# dual_output_buck_regulator.net
KiCad netlist of a schematic drawn in EAGLE
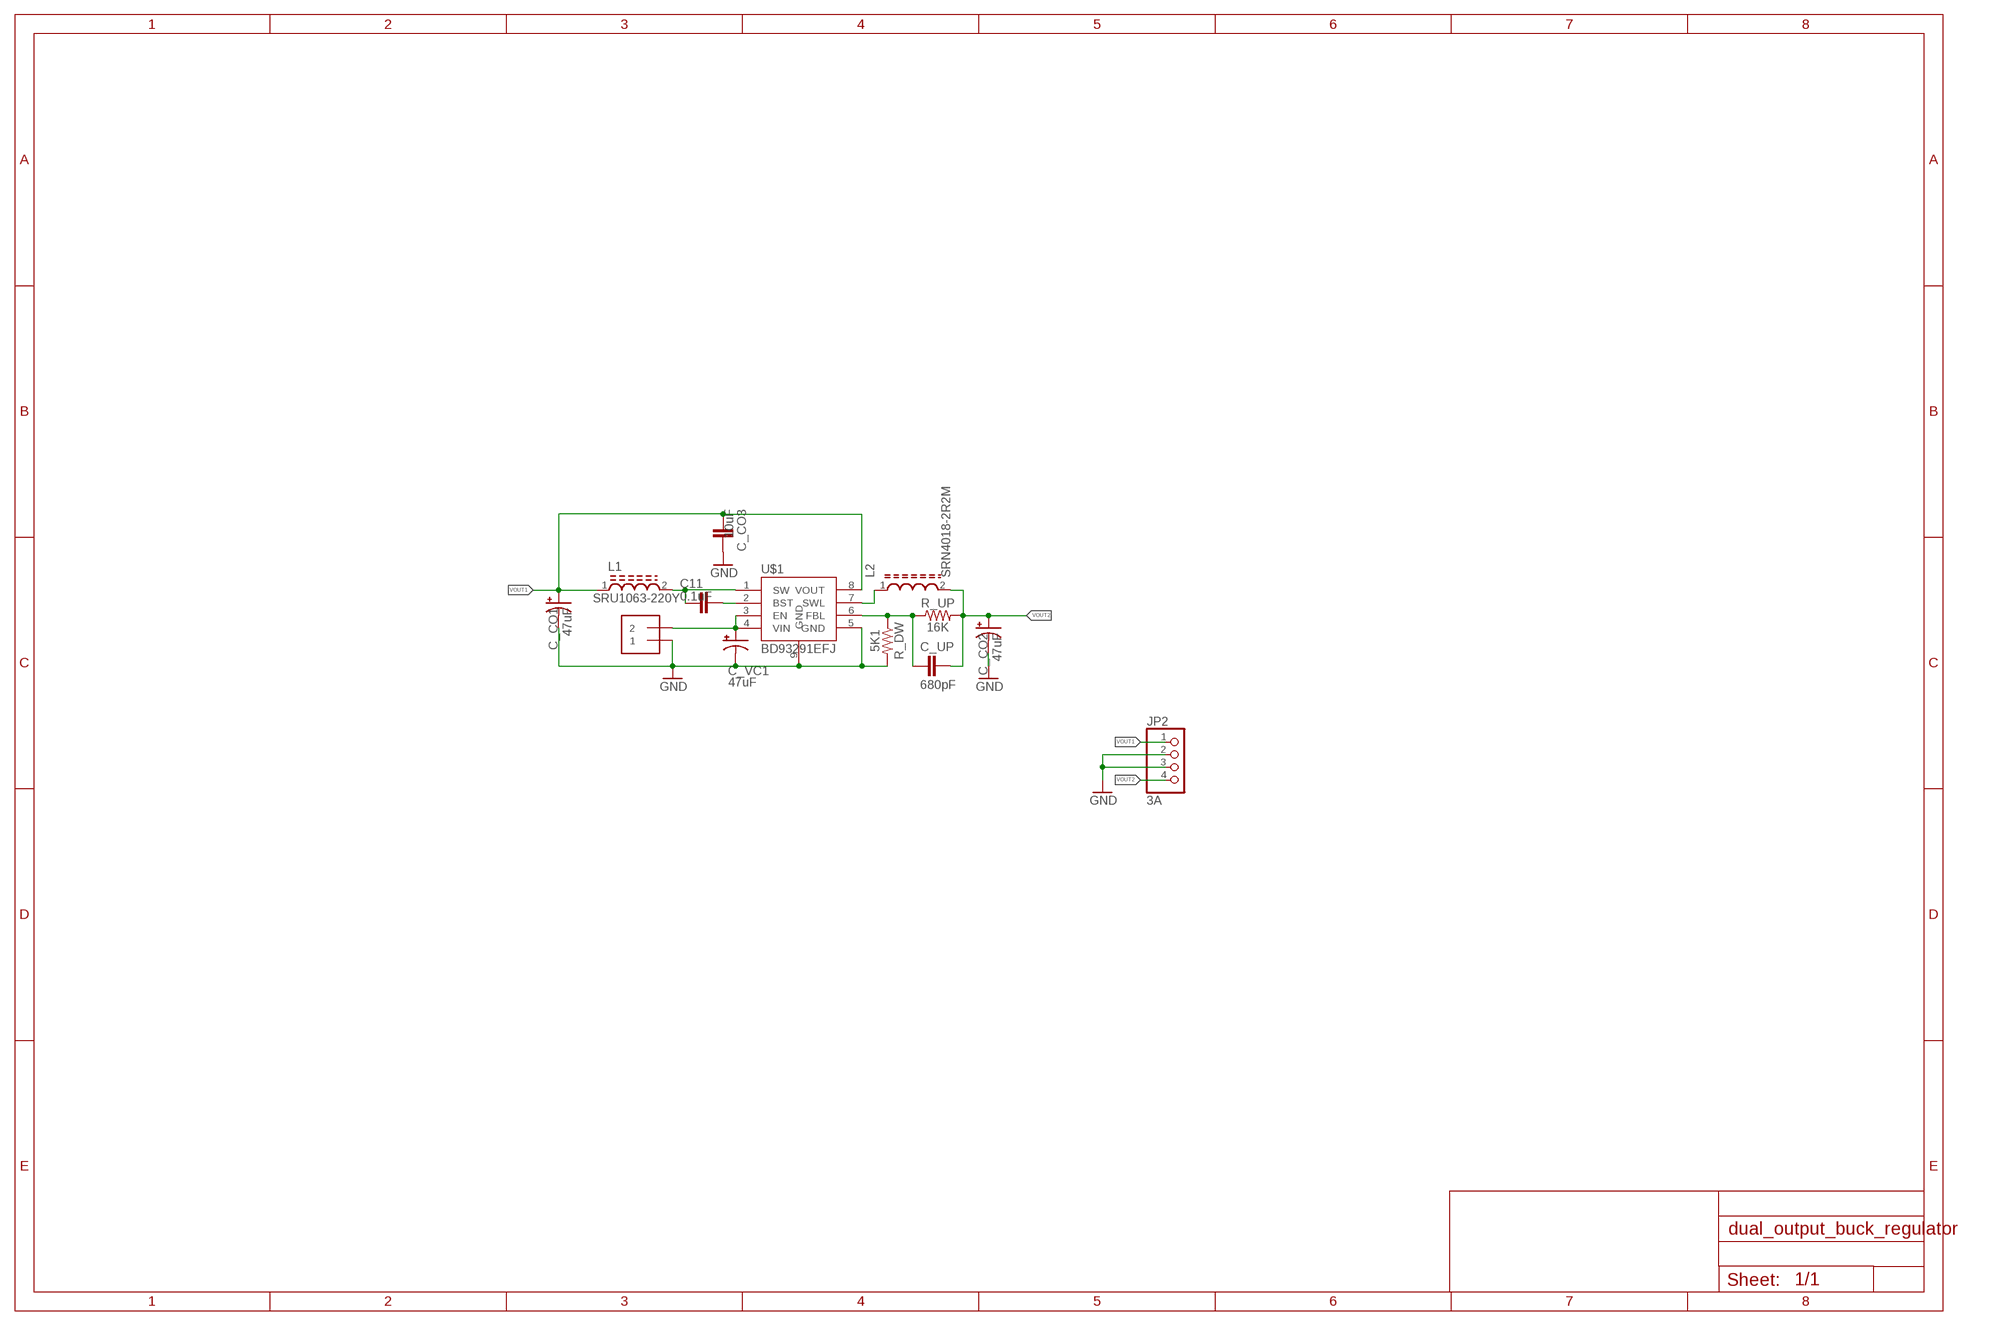
[diagram p0: schematic, sheet 1]

(export (version "E")
  (design (tool "Eeschema 10.0.6"))
  (components
    (comp (ref "C11")
      (value "0.1uF")
      (footprint "eagle-import:0603")
      (libsource (lib "eagle-import") (part "0.1UF-0603-25V-(+80/-20%)"))
    )
    (comp (ref "C_CO1")
      (value "47uF")
      (footprint "eagle-import:PANASONIC_C")
      (libsource (lib "eagle-import") (part "22UF-POLAR-PANASONIC_C-35V-20%"))
    )
    (comp (ref "C_CO2")
      (value "47uF")
      (footprint "eagle-import:PANASONIC_C")
      (libsource (lib "eagle-import") (part "22UF-POLAR-PANASONIC_C-35V-20%"))
    )
    (comp (ref "C_CO3")
      (value "10uF")
      (footprint "eagle-import:0603")
      (libsource (lib "eagle-import") (part "0.1UF-0603-25V-(+80/-20%)"))
    )
    (comp (ref "C_UP")
      (value "680pF")
      (footprint "eagle-import:0603")
      (libsource (lib "eagle-import") (part "0.1UF-0603-25V-(+80/-20%)"))
    )
    (comp (ref "C_VC1")
      (value "47uF")
      (footprint "eagle-import:PANASONIC_C")
      (libsource (lib "eagle-import") (part "22UF-POLAR-PANASONIC_C-35V-20%"))
    )
    (comp (ref "J1")
      (value "1X2-3.5MM")
      (footprint "eagle-import:1X2-3.5MM")
      (libsource (lib "eagle-import") (part "1X2-3.5MM"))
    )
    (comp (ref "JP2")
      (value "3A")
      (footprint "eagle-import:1X04")
      (libsource (lib "eagle-import") (part "PINHD-1X4"))
    )
    (comp (ref "L1")
      (value "SRU1063-220Y")
      (footprint "eagle-import:IND_SRU1063-220Y")
      (fields (field (name "MF") "Bourns"))
      (libsource (lib "eagle-import") (part "SRU1063-220Y"))
    )
    (comp (ref "L2")
      (value "SRN4018-2R2M")
      (footprint "eagle-import:INDP4040X180N")
      (fields (field (name "MF") "Bourns") (field (name "MP") "SRN4018-2R7M"))
      (libsource (lib "eagle-import") (part "SRN4018-2R7M"))
    )
    (comp (ref "R_DW")
      (value "5K1")
      (footprint "eagle-import:0603")
      (libsource (lib "eagle-import") (part "10KOHM-0603-1/10W-1%"))
    )
    (comp (ref "R_UP")
      (value "16K")
      (footprint "eagle-import:0603")
      (libsource (lib "eagle-import") (part "10KOHM-0603-1/10W-1%"))
    )
    (comp (ref "U$1")
      (value "BD93291EFJ")
      (footprint "eagle-import:SOIC127P600X100-9N")
      (libsource (lib "eagle-import") (part "BD93291EFJ"))
    )
  )
  (nets
    (net (code "1") (name "GND") (class "Default")
      (node (ref "C_CO1") (pin "-") (pinfunction "-_-") (pintype "passive"))
      (node (ref "C_CO2") (pin "-") (pinfunction "-_-") (pintype "passive"))
      (node (ref "C_CO3") (pin "1") (pinfunction "1_1") (pintype "passive"))
      (node (ref "C_VC1") (pin "-") (pinfunction "-_-") (pintype "passive"))
      (node (ref "J1") (pin "1") (pinfunction "1_1") (pintype "passive"))
      (node (ref "JP2") (pin "2") (pinfunction "2_2") (pintype "passive"))
      (node (ref "JP2") (pin "3") (pinfunction "3_3") (pintype "passive"))
      (node (ref "R_DW") (pin "2") (pinfunction "2_2") (pintype "passive"))
      (node (ref "U$1") (pin "5") (pinfunction "GND_5") (pintype "bidirectional"))
      (node (ref "U$1") (pin "9") (pinfunction "GND_9") (pintype "bidirectional"))
    )
    (net (code "2") (name "Net-(U$1-BST)") (class "Default")
      (node (ref "C11") (pin "1") (pinfunction "1_1") (pintype "passive"))
      (node (ref "U$1") (pin "2") (pinfunction "BST_2") (pintype "bidirectional"))
    )
    (net (code "3") (name "Net-(U$1-EN)") (class "Default")
      (node (ref "C_VC1") (pin "+") (pinfunction "+_+") (pintype "passive"))
      (node (ref "J1") (pin "2") (pinfunction "2_2") (pintype "passive"))
      (node (ref "U$1") (pin "3") (pinfunction "EN_3") (pintype "bidirectional"))
      (node (ref "U$1") (pin "4") (pinfunction "VIN_4") (pintype "bidirectional"))
    )
    (net (code "4") (name "Net-(U$1-FBL)") (class "Default")
      (node (ref "C_UP") (pin "2") (pinfunction "2_2") (pintype "passive"))
      (node (ref "R_DW") (pin "1") (pinfunction "1_1") (pintype "passive"))
      (node (ref "R_UP") (pin "1") (pinfunction "1_1") (pintype "passive"))
      (node (ref "U$1") (pin "6") (pinfunction "FBL_6") (pintype "bidirectional"))
    )
    (net (code "5") (name "Net-(U$1-SW)") (class "Default")
      (node (ref "C11") (pin "2") (pinfunction "2_2") (pintype "passive"))
      (node (ref "L1") (pin "2") (pinfunction "2_2") (pintype "passive"))
      (node (ref "U$1") (pin "1") (pinfunction "SW_1") (pintype "bidirectional"))
    )
    (net (code "6") (name "Net-(U$1-SWL)") (class "Default")
      (node (ref "L2") (pin "1") (pinfunction "1_1") (pintype "passive"))
      (node (ref "U$1") (pin "7") (pinfunction "SWL_7") (pintype "bidirectional"))
    )
    (net (code "7") (name "VOUT1") (class "Default")
      (node (ref "C_CO1") (pin "+") (pinfunction "+_+") (pintype "passive"))
      (node (ref "C_CO3") (pin "2") (pinfunction "2_2") (pintype "passive"))
      (node (ref "JP2") (pin "1") (pinfunction "1_1") (pintype "passive"))
      (node (ref "L1") (pin "1") (pinfunction "1_1") (pintype "passive"))
      (node (ref "U$1") (pin "8") (pinfunction "VOUT_8") (pintype "bidirectional"))
    )
    (net (code "8") (name "VOUT2") (class "Default")
      (node (ref "C_CO2") (pin "+") (pinfunction "+_+") (pintype "passive"))
      (node (ref "C_UP") (pin "1") (pinfunction "1_1") (pintype "passive"))
      (node (ref "JP2") (pin "4") (pinfunction "4_4") (pintype "passive"))
      (node (ref "L2") (pin "2") (pinfunction "2_2") (pintype "passive"))
      (node (ref "R_UP") (pin "2") (pinfunction "2_2") (pintype "passive"))
    )
  )
)
